# USB-C_Power_Supply.net
KiCad netlist of a schematic drawn in Altium Designer
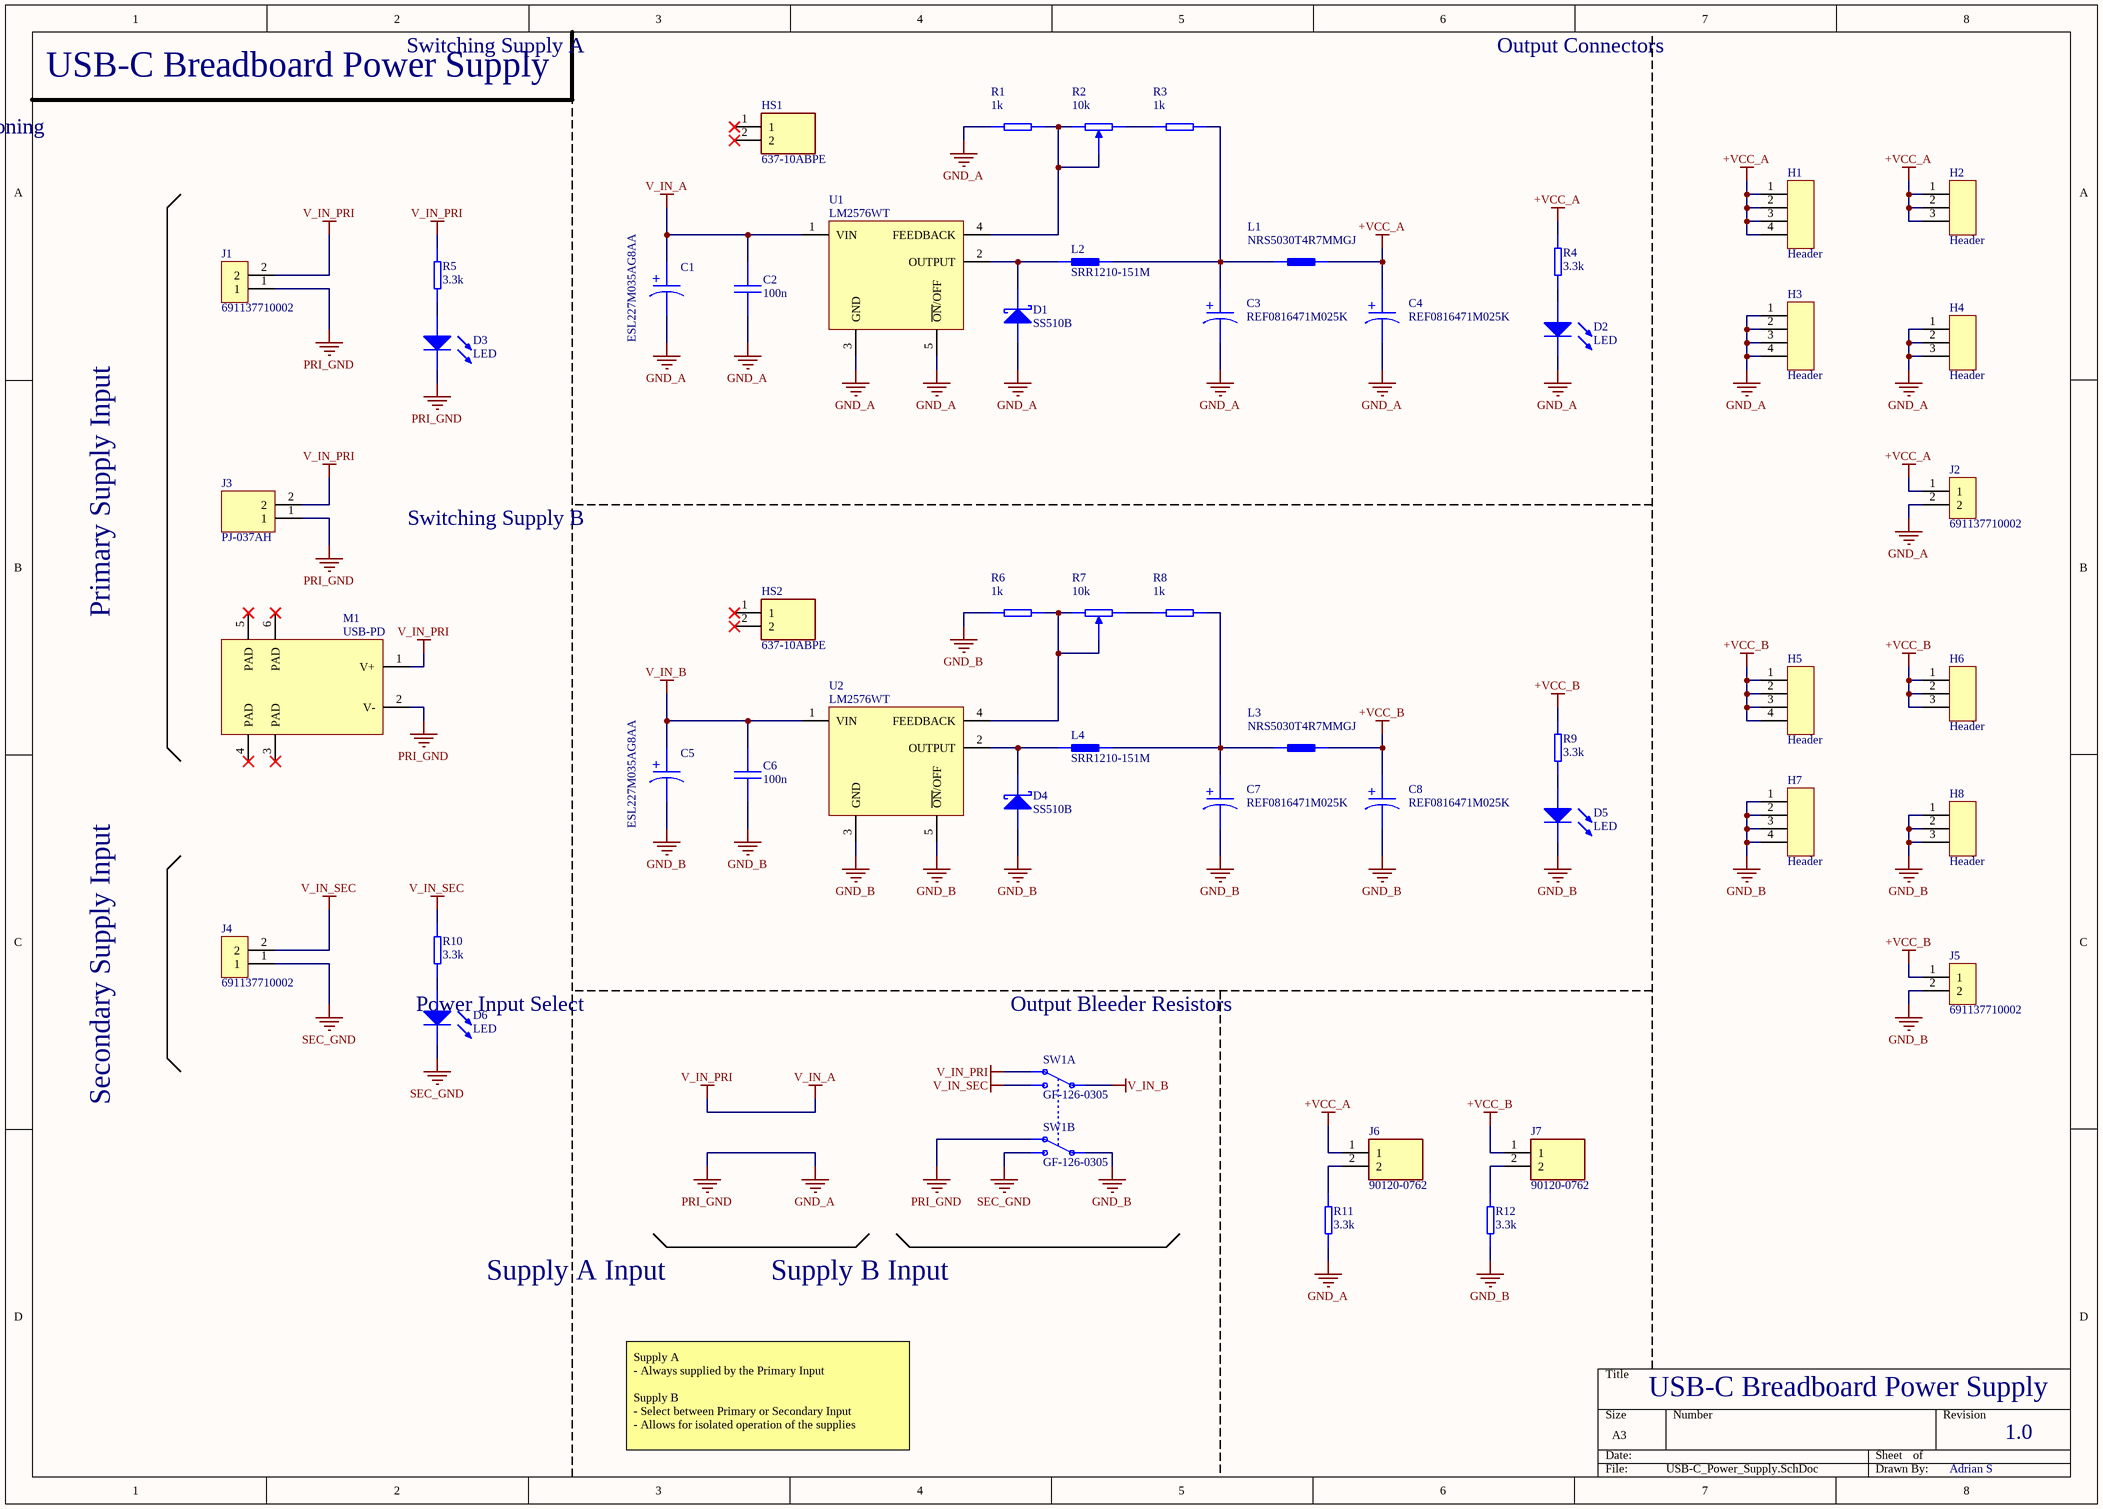
[diagram p0: USB-C_Power_Supply.SchDoc]

(export (version "E")
  (design (tool "Eeschema 10.0.6"))
  (components
    (comp (ref "C1")
      (value "ESL227M035AG8AA")
      (footprint "CAPTH8.00X18.00-3.50")
      (description "Capacitor Polarised")
      (fields (field (name "MOUSER PART NUMBER") "80-ESL227M035AG8AA"))
      (libsource (lib "TD") (part "ESL227M035AG8AA"))
    )
    (comp (ref "C2")
      (value "100n")
      (footprint "CAP0805")
      (description "Non Polarized Capacitor")
      (libsource (lib "TD") (part "Capacitor - Non Polarized"))
    )
    (comp (ref "C3")
      (value "REF0816471M025K")
      (footprint "CAPTH8.00X16.00-3.50")
      (description "Capacitor Polarised")
      (fields (field (name "MOUSER PART NUMBER") "581-REF0816471M025K"))
      (libsource (lib "TD") (part "REF0816471M025K"))
    )
    (comp (ref "C4")
      (value "REF0816471M025K")
      (footprint "CAPTH8.00X16.00-3.50")
      (description "Capacitor Polarised")
      (fields (field (name "MOUSER PART NUMBER") "581-REF0816471M025K"))
      (libsource (lib "TD") (part "REF0816471M025K"))
    )
    (comp (ref "C5")
      (value "ESL227M035AG8AA")
      (footprint "CAPTH8.00X18.00-3.50")
      (description "Capacitor Polarised")
      (fields (field (name "MOUSER PART NUMBER") "80-ESL227M035AG8AA"))
      (libsource (lib "TD") (part "ESL227M035AG8AA"))
    )
    (comp (ref "C6")
      (value "100n")
      (footprint "CAP0805")
      (description "Non Polarized Capacitor")
      (libsource (lib "TD") (part "Capacitor - Non Polarized"))
    )
    (comp (ref "C7")
      (value "REF0816471M025K")
      (footprint "CAPTH8.00X16.00-3.50")
      (description "Capacitor Polarised")
      (fields (field (name "MOUSER PART NUMBER") "581-REF0816471M025K"))
      (libsource (lib "TD") (part "REF0816471M025K"))
    )
    (comp (ref "C8")
      (value "REF0816471M025K")
      (footprint "CAPTH8.00X16.00-3.50")
      (description "Capacitor Polarised")
      (fields (field (name "MOUSER PART NUMBER") "581-REF0816471M025K"))
      (libsource (lib "TD") (part "REF0816471M025K"))
    )
    (comp (ref "D1")
      (value "SS510B")
      (footprint "DO-214AC (SMA)")
      (description "Diode")
      (libsource (lib "TD") (part "SS510B"))
    )
    (comp (ref "D2")
      (value "LED")
      (footprint "LEDM2012X80N")
      (description "General Purpose LED")
      (libsource (lib "TD") (part "LED"))
    )
    (comp (ref "D3")
      (value "LED")
      (footprint "LEDM2012X80N")
      (description "General Purpose LED")
      (libsource (lib "TD") (part "LED"))
    )
    (comp (ref "D4")
      (value "SS510B")
      (footprint "DO-214AC (SMA)")
      (description "Diode")
      (libsource (lib "TD") (part "SS510B"))
    )
    (comp (ref "D5")
      (value "LED")
      (footprint "LEDM2012X80N")
      (description "General Purpose LED")
      (libsource (lib "TD") (part "LED"))
    )
    (comp (ref "D6")
      (value "LED")
      (footprint "LEDM2012X80N")
      (description "General Purpose LED")
      (libsource (lib "TD") (part "LED"))
    )
    (comp (ref "H1")
      (value "Header")
      (footprint "Header_1X4")
      (description "4-Pin Header")
      (libsource (lib "TD") (part "4-Pin Header"))
    )
    (comp (ref "H2")
      (value "Header")
      (footprint "Header_1X3")
      (description "3-Pin Header")
      (libsource (lib "TD") (part "3-Pin Header"))
    )
    (comp (ref "H3")
      (value "Header")
      (footprint "Header_1X4")
      (description "4-Pin Header")
      (libsource (lib "TD") (part "4-Pin Header"))
    )
    (comp (ref "H4")
      (value "Header")
      (footprint "Header_1X3")
      (description "3-Pin Header")
      (libsource (lib "TD") (part "3-Pin Header"))
    )
    (comp (ref "H5")
      (value "Header")
      (footprint "Header_1X4")
      (description "4-Pin Header")
      (libsource (lib "TD") (part "4-Pin Header"))
    )
    (comp (ref "H6")
      (value "Header")
      (footprint "Header_1X3")
      (description "3-Pin Header")
      (libsource (lib "TD") (part "3-Pin Header"))
    )
    (comp (ref "H7")
      (value "Header")
      (footprint "Header_1X4")
      (description "4-Pin Header")
      (libsource (lib "TD") (part "4-Pin Header"))
    )
    (comp (ref "H8")
      (value "Header")
      (footprint "Header_1X3")
      (description "3-Pin Header")
      (libsource (lib "TD") (part "3-Pin Header"))
    )
    (comp (ref "HS1")
      (value "637-10ABPE")
      (footprint "63710ABPE")
      (description "Undefined or Miscellaneous")
      (fields (field (name "MOUSER PART NUMBER") "567-637-10ABPE"))
      (libsource (lib "*") (part "637-10ABPE"))
    )
    (comp (ref "HS2")
      (value "637-10ABPE")
      (footprint "63710ABPE")
      (description "Undefined or Miscellaneous")
      (fields (field (name "MOUSER PART NUMBER") "567-637-10ABPE"))
      (libsource (lib "*") (part "637-10ABPE"))
    )
    (comp (ref "J1")
      (value "691137710002")
      (footprint "SHDR2W70P0X500_1X2_1000X750X1160P")
      (description "Connector")
      (fields (field (name "MOUSER PART NUMBER") "710-691137710002"))
      (libsource (lib "TD") (part "691137710002"))
    )
    (comp (ref "J2")
      (value "691137710002")
      (footprint "SHDR2W70P0X500_1X2_1000X750X1160P")
      (description "Connector")
      (fields (field (name "MOUSER PART NUMBER") "710-691137710002"))
      (libsource (lib "") (part "691137710002_1"))
    )
    (comp (ref "J3")
      (value "PJ-037AH")
      (footprint "PJ037AH")
      (description "Connector")
      (fields (field (name "MOUSER PART NUMBER") "490-PJ-037AH"))
      (libsource (lib "TD") (part "PJ-037AH"))
    )
    (comp (ref "J4")
      (value "691137710002")
      (footprint "SHDR2W70P0X500_1X2_1000X750X1160P")
      (description "Connector")
      (fields (field (name "MOUSER PART NUMBER") "710-691137710002"))
      (libsource (lib "TD") (part "691137710002"))
    )
    (comp (ref "J5")
      (value "691137710002")
      (footprint "SHDR2W70P0X500_1X2_1000X750X1160P")
      (description "Connector")
      (fields (field (name "MOUSER PART NUMBER") "710-691137710002"))
      (libsource (lib "") (part "691137710002_1"))
    )
    (comp (ref "J6")
      (value "90120-0762")
      (footprint "Header_1X2")
      (description "Connector")
      (fields (field (name "MOUSER PART NUMBER") "538-90120-0762"))
      (libsource (lib "SamacSys") (part "90120-0762"))
    )
    (comp (ref "J7")
      (value "90120-0762")
      (footprint "Header_1X2")
      (description "Connector")
      (fields (field (name "MOUSER PART NUMBER") "538-90120-0762"))
      (libsource (lib "SamacSys") (part "90120-0762"))
    )
    (comp (ref "L1")
      (value "NRS5030T4R7MMGJ")
      (footprint "IND (4.9mmx4.9mm)")
      (description "Inductor")
      (fields (field (name "MOUSER PART NUMBER") "963-NRS5030T4R7MMGJ"))
      (libsource (lib "TD") (part "NRS5030T4R7MMGJ"))
    )
    (comp (ref "L2")
      (value "SRR1210-151M")
      (footprint "INDPM120120X1000N-D")
      (description "Inductor")
      (fields (field (name "MOUSER PART NUMBER") "652-SRR1210-151M"))
      (libsource (lib "TD") (part "SRR1210-151M"))
    )
    (comp (ref "L3")
      (value "NRS5030T4R7MMGJ")
      (footprint "IND (4.9mmx4.9mm)")
      (description "Inductor")
      (fields (field (name "MOUSER PART NUMBER") "963-NRS5030T4R7MMGJ"))
      (libsource (lib "TD") (part "NRS5030T4R7MMGJ"))
    )
    (comp (ref "L4")
      (value "SRR1210-151M")
      (footprint "INDPM120120X1000N-D")
      (description "Inductor")
      (fields (field (name "MOUSER PART NUMBER") "652-SRR1210-151M"))
      (libsource (lib "TD") (part "SRR1210-151M"))
    )
    (comp (ref "M1")
      (value "USB-PD")
      (footprint "USB_C-PD")
      (libsource (lib "IEEE_Workshop_SCH") (part "USB-PD"))
    )
    (comp (ref "R1")
      (value "1k")
      (footprint "RESC0805")
      (description "Resistor")
      (libsource (lib "TD") (part "Resistor"))
    )
    (comp (ref "R2")
      (value "10k")
      (footprint "3339P1103LF - Modified")
      (description "Potentionmeter")
      (libsource (lib "TD") (part "Potentiometer"))
    )
    (comp (ref "R3")
      (value "1k")
      (footprint "RESC0805")
      (description "Resistor")
      (libsource (lib "TD") (part "Resistor"))
    )
    (comp (ref "R4")
      (value "3.3k")
      (footprint "RESC0805")
      (description "Resistor")
      (libsource (lib "TD") (part "Resistor"))
    )
    (comp (ref "R5")
      (value "3.3k")
      (footprint "RESC0805")
      (description "Resistor")
      (libsource (lib "TD") (part "Resistor"))
    )
    (comp (ref "R6")
      (value "1k")
      (footprint "RESC0805")
      (description "Resistor")
      (libsource (lib "TD") (part "Resistor"))
    )
    (comp (ref "R7")
      (value "10k")
      (footprint "3339P1103LF - Modified")
      (description "Potentionmeter")
      (libsource (lib "TD") (part "Potentiometer"))
    )
    (comp (ref "R8")
      (value "1k")
      (footprint "RESC0805")
      (description "Resistor")
      (libsource (lib "TD") (part "Resistor"))
    )
    (comp (ref "R9")
      (value "3.3k")
      (footprint "RESC0805")
      (description "Resistor")
      (libsource (lib "TD") (part "Resistor"))
    )
    (comp (ref "R10")
      (value "3.3k")
      (footprint "RESC0805")
      (description "Resistor")
      (libsource (lib "TD") (part "Resistor"))
    )
    (comp (ref "R11")
      (value "3.3k")
      (footprint "RESC0805")
      (description "Resistor")
      (libsource (lib "TD") (part "Resistor"))
    )
    (comp (ref "R12")
      (value "3.3k")
      (footprint "RESC0805")
      (description "Resistor")
      (libsource (lib "TD") (part "Resistor"))
    )
    (comp (ref "SW1")
      (value "GF-126-0305")
      (footprint "GF1260305")
      (description "DPDT Slide Switch")
      (libsource (lib "TD") (part "GF-126-0305"))
    )
    (comp (ref "U1")
      (value "LM2576WT")
      (footprint "TO-220-5")
      (description "Integrated Circuit")
      (fields
        (field (name "MANUFACTURER_PART_NUMBER") "LM2576WU-TR")
        (field (name "MOUSER PART NUMBER") "998-LM2576WT")
      )
      (libsource (lib "TD") (part "LM2576WT"))
    )
    (comp (ref "U2")
      (value "LM2576WT")
      (footprint "TO-220-5")
      (description "Integrated Circuit")
      (fields
        (field (name "MANUFACTURER_PART_NUMBER") "LM2576WU-TR")
        (field (name "MOUSER PART NUMBER") "998-LM2576WT")
      )
      (libsource (lib "TD") (part "LM2576WT"))
    )
  )
  (nets
    (net (code "1") (name "+VCC_A") (class "Default")
      (node (ref "C4") (pin "1") (pintype "passive"))
      (node (ref "H1") (pin "1") (pintype "passive"))
      (node (ref "H1") (pin "2") (pintype "passive"))
      (node (ref "H1") (pin "3") (pintype "passive"))
      (node (ref "H1") (pin "4") (pintype "passive"))
      (node (ref "H2") (pin "1") (pintype "passive"))
      (node (ref "H2") (pin "2") (pintype "passive"))
      (node (ref "H2") (pin "3") (pintype "passive"))
      (node (ref "J2") (pin "1") (pinfunction "1_1") (pintype "passive"))
      (node (ref "J6") (pin "1") (pinfunction "1_1") (pintype "passive"))
      (node (ref "L1") (pin "2") (pintype "passive"))
      (node (ref "R4") (pin "1") (pintype "passive"))
    )
    (net (code "2") (name "+VCC_B") (class "Default")
      (node (ref "C8") (pin "1") (pintype "passive"))
      (node (ref "H5") (pin "1") (pintype "passive"))
      (node (ref "H5") (pin "2") (pintype "passive"))
      (node (ref "H5") (pin "3") (pintype "passive"))
      (node (ref "H5") (pin "4") (pintype "passive"))
      (node (ref "H6") (pin "1") (pintype "passive"))
      (node (ref "H6") (pin "2") (pintype "passive"))
      (node (ref "H6") (pin "3") (pintype "passive"))
      (node (ref "J5") (pin "1") (pinfunction "1_1") (pintype "passive"))
      (node (ref "J7") (pin "1") (pinfunction "1_1") (pintype "passive"))
      (node (ref "L3") (pin "2") (pintype "passive"))
      (node (ref "R9") (pin "1") (pintype "passive"))
    )
    (net (code "3") (name "GND_A") (class "Default")
      (node (ref "C1") (pin "2") (pintype "passive"))
      (node (ref "C2") (pin "2") (pintype "passive"))
      (node (ref "C3") (pin "2") (pintype "passive"))
      (node (ref "C4") (pin "2") (pintype "passive"))
      (node (ref "D1") (pin "2") (pinfunction "A_2") (pintype "passive"))
      (node (ref "D2") (pin "1") (pinfunction "K_1") (pintype "passive"))
      (node (ref "D3") (pin "1") (pinfunction "K_1") (pintype "passive"))
      (node (ref "H3") (pin "1") (pintype "passive"))
      (node (ref "H3") (pin "2") (pintype "passive"))
      (node (ref "H3") (pin "3") (pintype "passive"))
      (node (ref "H3") (pin "4") (pintype "passive"))
      (node (ref "H4") (pin "1") (pintype "passive"))
      (node (ref "H4") (pin "2") (pintype "passive"))
      (node (ref "H4") (pin "3") (pintype "passive"))
      (node (ref "J1") (pin "1") (pinfunction "1_1") (pintype "passive"))
      (node (ref "J2") (pin "2") (pinfunction "2_2") (pintype "passive"))
      (node (ref "J3") (pin "1") (pinfunction "1_1") (pintype "passive"))
      (node (ref "M1") (pin "2") (pinfunction "V-_2") (pintype "passive"))
      (node (ref "R1") (pin "2") (pintype "passive"))
      (node (ref "R11") (pin "2") (pintype "passive"))
      (node (ref "SW1") (pin "6") (pintype "passive"))
      (node (ref "U1") (pin "3") (pinfunction "GND_3") (pintype "passive"))
      (node (ref "U1") (pin "5") (pinfunction "~{ON}/OFF_5") (pintype "passive"))
    )
    (net (code "4") (name "GND_B") (class "Default")
      (node (ref "C5") (pin "2") (pintype "passive"))
      (node (ref "C6") (pin "2") (pintype "passive"))
      (node (ref "C7") (pin "2") (pintype "passive"))
      (node (ref "C8") (pin "2") (pintype "passive"))
      (node (ref "D4") (pin "2") (pinfunction "A_2") (pintype "passive"))
      (node (ref "D5") (pin "1") (pinfunction "K_1") (pintype "passive"))
      (node (ref "H7") (pin "1") (pintype "passive"))
      (node (ref "H7") (pin "2") (pintype "passive"))
      (node (ref "H7") (pin "3") (pintype "passive"))
      (node (ref "H7") (pin "4") (pintype "passive"))
      (node (ref "H8") (pin "1") (pintype "passive"))
      (node (ref "H8") (pin "2") (pintype "passive"))
      (node (ref "H8") (pin "3") (pintype "passive"))
      (node (ref "J5") (pin "2") (pinfunction "2_2") (pintype "passive"))
      (node (ref "R12") (pin "2") (pintype "passive"))
      (node (ref "R6") (pin "2") (pintype "passive"))
      (node (ref "SW1") (pin "5") (pintype "passive"))
      (node (ref "U2") (pin "3") (pinfunction "GND_3") (pintype "passive"))
      (node (ref "U2") (pin "5") (pinfunction "~{ON}/OFF_5") (pintype "passive"))
    )
    (net (code "5") (name "Net-(C3-Pad1)") (class "Default")
      (node (ref "C3") (pin "1") (pintype "passive"))
      (node (ref "L1") (pin "1") (pintype "passive"))
      (node (ref "L2") (pin "2") (pintype "passive"))
      (node (ref "R3") (pin "1") (pintype "passive"))
    )
    (net (code "6") (name "Net-(C7-Pad1)") (class "Default")
      (node (ref "C7") (pin "1") (pintype "passive"))
      (node (ref "L3") (pin "1") (pintype "passive"))
      (node (ref "L4") (pin "2") (pintype "passive"))
      (node (ref "R8") (pin "1") (pintype "passive"))
    )
    (net (code "7") (name "Net-(D1-K)") (class "Default")
      (node (ref "D1") (pin "1") (pinfunction "K_1") (pintype "passive"))
      (node (ref "L2") (pin "1") (pintype "passive"))
      (node (ref "U1") (pin "2") (pinfunction "OUTPUT_2") (pintype "passive"))
    )
    (net (code "8") (name "Net-(D2-A)") (class "Default")
      (node (ref "D2") (pin "2") (pinfunction "A_2") (pintype "passive"))
      (node (ref "R4") (pin "2") (pintype "passive"))
    )
    (net (code "9") (name "Net-(D3-A)") (class "Default")
      (node (ref "D3") (pin "2") (pinfunction "A_2") (pintype "passive"))
      (node (ref "R5") (pin "2") (pintype "passive"))
    )
    (net (code "10") (name "Net-(D4-K)") (class "Default")
      (node (ref "D4") (pin "1") (pinfunction "K_1") (pintype "passive"))
      (node (ref "L4") (pin "1") (pintype "passive"))
      (node (ref "U2") (pin "2") (pinfunction "OUTPUT_2") (pintype "passive"))
    )
    (net (code "11") (name "Net-(D5-A)") (class "Default")
      (node (ref "D5") (pin "2") (pinfunction "A_2") (pintype "passive"))
      (node (ref "R9") (pin "2") (pintype "passive"))
    )
    (net (code "12") (name "Net-(D6-A)") (class "Default")
      (node (ref "D6") (pin "2") (pinfunction "A_2") (pintype "passive"))
      (node (ref "R10") (pin "2") (pintype "passive"))
    )
    (net (code "13") (name "Net-(J6-Pad2)") (class "Default")
      (node (ref "J6") (pin "2") (pinfunction "2_2") (pintype "passive"))
      (node (ref "R11") (pin "1") (pintype "passive"))
    )
    (net (code "14") (name "Net-(J7-Pad2)") (class "Default")
      (node (ref "J7") (pin "2") (pinfunction "2_2") (pintype "passive"))
      (node (ref "R12") (pin "1") (pintype "passive"))
    )
    (net (code "15") (name "Net-(R2-Pad1)") (class "Default")
      (node (ref "R2") (pin "1") (pintype "passive"))
      (node (ref "R3") (pin "2") (pintype "passive"))
    )
    (net (code "16") (name "Net-(R7-Pad1)") (class "Default")
      (node (ref "R7") (pin "1") (pintype "passive"))
      (node (ref "R8") (pin "2") (pintype "passive"))
    )
    (net (code "17") (name "Net-(U1-FEEDBACK)") (class "Default")
      (node (ref "R1") (pin "1") (pintype "passive"))
      (node (ref "R2") (pin "2") (pintype "passive"))
      (node (ref "R2") (pin "3") (pintype "passive"))
      (node (ref "U1") (pin "4") (pinfunction "FEEDBACK_4") (pintype "passive"))
    )
    (net (code "18") (name "Net-(U2-FEEDBACK)") (class "Default")
      (node (ref "R6") (pin "1") (pintype "passive"))
      (node (ref "R7") (pin "2") (pintype "passive"))
      (node (ref "R7") (pin "3") (pintype "passive"))
      (node (ref "U2") (pin "4") (pinfunction "FEEDBACK_4") (pintype "passive"))
    )
    (net (code "19") (name "SEC_GND") (class "Default")
      (node (ref "D6") (pin "1") (pinfunction "K_1") (pintype "passive"))
      (node (ref "J4") (pin "1") (pinfunction "1_1") (pintype "passive"))
      (node (ref "SW1") (pin "4") (pintype "passive"))
    )
    (net (code "20") (name "V_IN_A") (class "Default")
      (node (ref "C1") (pin "1") (pintype "passive"))
      (node (ref "C2") (pin "1") (pintype "passive"))
      (node (ref "J1") (pin "2") (pinfunction "2_2") (pintype "passive"))
      (node (ref "J3") (pin "2") (pinfunction "2_2") (pintype "passive"))
      (node (ref "M1") (pin "1") (pinfunction "V+_1") (pintype "passive"))
      (node (ref "R5") (pin "1") (pintype "passive"))
      (node (ref "SW1") (pin "1") (pintype "passive"))
      (node (ref "U1") (pin "1") (pinfunction "VIN_1") (pintype "passive"))
    )
    (net (code "21") (name "V_IN_B") (class "Default")
      (node (ref "C5") (pin "1") (pintype "passive"))
      (node (ref "C6") (pin "1") (pintype "passive"))
      (node (ref "SW1") (pin "2") (pintype "passive"))
      (node (ref "U2") (pin "1") (pinfunction "VIN_1") (pintype "passive"))
    )
    (net (code "22") (name "V_IN_SEC") (class "Default")
      (node (ref "J4") (pin "2") (pinfunction "2_2") (pintype "passive"))
      (node (ref "R10") (pin "1") (pintype "passive"))
      (node (ref "SW1") (pin "3") (pintype "passive"))
    )
    (net (code "23") (name "unconnected-(HS1-Pad1)") (class "Default")
      (node (ref "HS1") (pin "1") (pinfunction "1_1") (pintype "passive+no_connect"))
    )
    (net (code "24") (name "unconnected-(HS1-Pad2)") (class "Default")
      (node (ref "HS1") (pin "2") (pinfunction "2_2") (pintype "passive+no_connect"))
    )
    (net (code "25") (name "unconnected-(HS2-Pad1)") (class "Default")
      (node (ref "HS2") (pin "1") (pinfunction "1_1") (pintype "passive+no_connect"))
    )
    (net (code "26") (name "unconnected-(HS2-Pad2)") (class "Default")
      (node (ref "HS2") (pin "2") (pinfunction "2_2") (pintype "passive+no_connect"))
    )
    (net (code "27") (name "unconnected-(M1-PAD-Pad3)") (class "Default")
      (node (ref "M1") (pin "3") (pinfunction "PAD_3") (pintype "passive+no_connect"))
    )
    (net (code "28") (name "unconnected-(M1-PAD-Pad4)") (class "Default")
      (node (ref "M1") (pin "4") (pinfunction "PAD_4") (pintype "passive+no_connect"))
    )
    (net (code "29") (name "unconnected-(M1-PAD-Pad5)") (class "Default")
      (node (ref "M1") (pin "5") (pinfunction "PAD_5") (pintype "passive+no_connect"))
    )
    (net (code "30") (name "unconnected-(M1-PAD-Pad6)") (class "Default")
      (node (ref "M1") (pin "6") (pinfunction "PAD_6") (pintype "passive+no_connect"))
    )
  )
)
